# Sheet1.net
KiCad netlist of a schematic drawn in Altium Designer
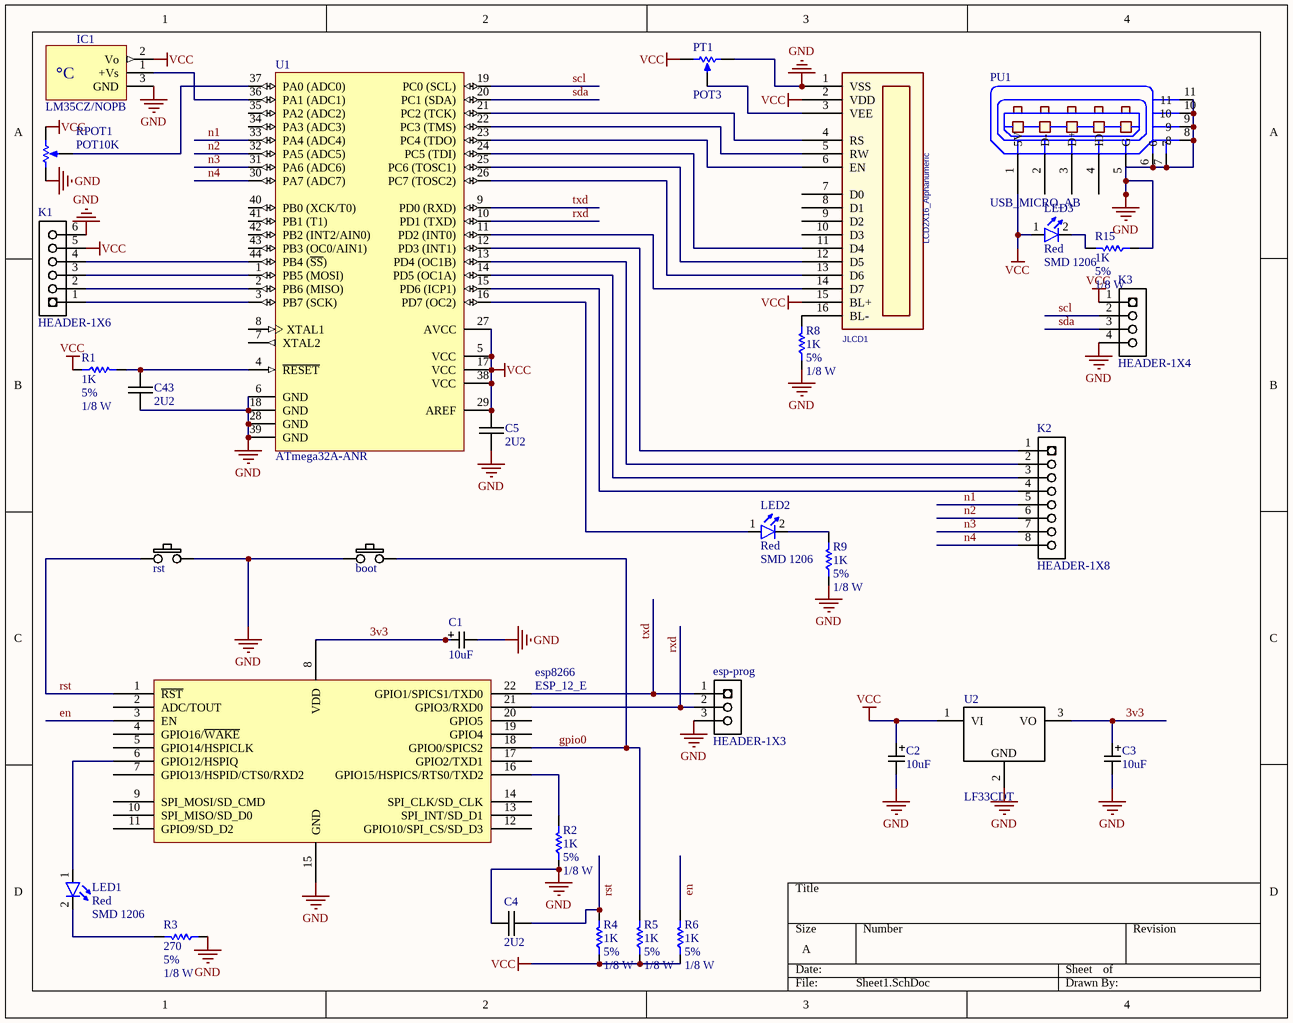
[diagram p0: Sheet1.SchDoc]

(export (version "E")
  (design (tool "Eeschema 10.0.6"))
  (components
    (comp (ref "boot")
      (value "SW-PB-BLACK-SMD")
      (footprint "SW-PB-SMD")
      (description "PUSHBUTTON SWITCH 6MM SMD")
      (libsource (lib "vh_altium_library") (part "SW-PB-BLACK-SMD"))
    )
    (comp (ref "C1")
      (value "10uF")
      (footprint "CAP-B")
      (description "tantalium capacitor")
      (fields (field (name "VOLTAGE") "16V"))
      (libsource (lib "amir_altium_lib") (part "cap"))
    )
    (comp (ref "C2")
      (value "10uF")
      (footprint "CAP-B")
      (description "tantalium capacitor")
      (fields (field (name "VOLTAGE") "16V"))
      (libsource (lib "amir_altium_lib") (part "cap"))
    )
    (comp (ref "C3")
      (value "10uF")
      (footprint "CAP-B")
      (description "tantalium capacitor")
      (fields (field (name "VOLTAGE") "16V"))
      (libsource (lib "amir_altium_lib") (part "cap"))
    )
    (comp (ref "C4")
      (value "2U2")
      (footprint "1206C-GENERIC")
      (description "CAPACITOR 0603 CERAMIC")
      (libsource (lib "vh_altium_library") (part "1206C-2U2-50V"))
    )
    (comp (ref "C5")
      (value "2U2")
      (footprint "1206C-GENERIC")
      (description "CAPACITOR 0603 CERAMIC")
      (libsource (lib "vh_altium_library") (part "1206C-2U2-50V"))
    )
    (comp (ref "C43")
      (value "2U2")
      (footprint "1206C-GENERIC")
      (description "CAPACITOR 0603 CERAMIC")
      (libsource (lib "vh_altium_library") (part "1206C-2U2-50V"))
    )
    (comp (ref "esp-prog")
      (value "HEADER-1X3")
      (footprint "HEADER-1X3")
      (libsource (lib "vh_altium_library") (part "HEADER-1X3"))
    )
    (comp (ref "esp8266")
      (value "ESP_12_E")
      (footprint "ESP_12_E")
      (description "ESP-12 Wi-Fi Module by AI-Thinker")
      (libsource (lib "Morteza lib") (part "ESP_12_E"))
    )
    (comp (ref "IC1")
      (value "LM35CZ/NOPB")
      (footprint "TO-92AA-P127")
      (description "Precision Centigrade Temperature Sensor")
      (fields (field (name "MANUFACTURER") "NATIONAL SEMICONDUCTOR") (field (name "AUTHOR") "CERN DEM JLC"))
      (libsource (lib "Sensors") (part "LM35CZ/NOPB"))
    )
    (comp (ref "JLCD1") (value "LCD2X16_Alphanumeric") (libsource (lib "ALL") (part "LCD2X16_Alphanumeric")))
    (comp (ref "K1")
      (value "HEADER-1X6")
      (footprint "HEADER-1X6")
      (libsource (lib "vh_altium_library") (part "HEADER-1X6"))
    )
    (comp (ref "K2")
      (value "HEADER-1X8")
      (footprint "HEADER-1X8")
      (libsource (lib "vh_altium_library") (part "HEADER-1X8"))
    )
    (comp (ref "K3")
      (value "HEADER-1X4")
      (footprint "HEADER-1X4")
      (libsource (lib "vh_altium_library") (part "HEADER-1X4"))
    )
    (comp (ref "LED1")
      (value "Red")
      (footprint "LED SMD 1206")
      (description "LED")
      (fields
        (field (name "COLOR") "Red")
        (field (name "SIZE") "SMD 1206")
        (field (name "DESIGNER") "Saeid Jorablo")
      )
      (libsource (lib "Electrovolt Lib") (part "LED"))
    )
    (comp (ref "LED2")
      (value "Red")
      (footprint "LED SMD 1206")
      (description "LED")
      (fields
        (field (name "COLOR") "Red")
        (field (name "SIZE") "SMD 1206")
        (field (name "DESIGNER") "Saeid Jorablo")
      )
      (libsource (lib "Electrovolt Lib") (part "LED"))
    )
    (comp (ref "LED3")
      (value "Red")
      (footprint "LED SMD 1206")
      (description "LED")
      (fields
        (field (name "COLOR") "Red")
        (field (name "SIZE") "SMD 1206")
        (field (name "DESIGNER") "Saeid Jorablo")
      )
      (libsource (lib "Electrovolt Lib") (part "LED"))
    )
    (comp (ref "PT1")
      (value "POT3")
      (footprint "POT3")
      (description "Variable Potentiometer top adjust")
      (fields (field (name "DESIGNER") "Seyed Mohsen Ghasemian"))
      (libsource (lib "usefully_Library") (part "POT3"))
    )
    (comp (ref "PU1")
      (value "USB_MICRO_AB")
      (footprint "UUSB_AB_BM_SHS")
      (libsource (lib "ALL") (part "USB_MICRO_AB"))
    )
    (comp (ref "R1")
      (value "1K")
      (footprint "RES 1206 (3216X08L)")
      (description "Resistor")
      (fields (field (name "TOLERANCE") "5%") (field (name "POWER") "1/8 W"))
      (libsource (lib "Electrovolt Lib") (part "Resistor"))
    )
    (comp (ref "R2")
      (value "1K")
      (footprint "RES 1206 (3216X08L)")
      (description "Resistor")
      (fields (field (name "TOLERANCE") "5%") (field (name "POWER") "1/8 W"))
      (libsource (lib "Electrovolt Lib") (part "Resistor"))
    )
    (comp (ref "R3")
      (value "270")
      (footprint "RES 1206 (3216X08L)")
      (description "Resistor")
      (fields (field (name "TOLERANCE") "5%") (field (name "POWER") "1/8 W"))
      (libsource (lib "Electrovolt Lib") (part "Resistor"))
    )
    (comp (ref "R4")
      (value "1K")
      (footprint "RES 1206 (3216X08L)")
      (description "Resistor")
      (fields (field (name "TOLERANCE") "5%") (field (name "POWER") "1/8 W"))
      (libsource (lib "Electrovolt Lib") (part "Resistor"))
    )
    (comp (ref "R5")
      (value "1K")
      (footprint "RES 1206 (3216X08L)")
      (description "Resistor")
      (fields (field (name "TOLERANCE") "5%") (field (name "POWER") "1/8 W"))
      (libsource (lib "Electrovolt Lib") (part "Resistor"))
    )
    (comp (ref "R6")
      (value "1K")
      (footprint "RES 1206 (3216X08L)")
      (description "Resistor")
      (fields (field (name "TOLERANCE") "5%") (field (name "POWER") "1/8 W"))
      (libsource (lib "Electrovolt Lib") (part "Resistor"))
    )
    (comp (ref "R8")
      (value "1K")
      (footprint "RES 1206 (3216X08L)")
      (description "Resistor")
      (fields (field (name "TOLERANCE") "5%") (field (name "POWER") "1/8 W"))
      (libsource (lib "Electrovolt Lib") (part "Resistor"))
    )
    (comp (ref "R9")
      (value "1K")
      (footprint "RES 1206 (3216X08L)")
      (description "Resistor")
      (fields (field (name "TOLERANCE") "5%") (field (name "POWER") "1/8 W"))
      (libsource (lib "Electrovolt Lib") (part "Resistor"))
    )
    (comp (ref "R15")
      (value "1K")
      (footprint "RES 1206 (3216X08L)")
      (description "Resistor")
      (fields (field (name "TOLERANCE") "5%") (field (name "POWER") "1/8 W"))
      (libsource (lib "Electrovolt Lib") (part "Resistor"))
    )
    (comp (ref "RPOT1")
      (value "POT10K")
      (footprint "VOL_R")
      (description "Potentiometer")
      (fields (field (name "PUBLISHER") "Altium Limited"))
      (libsource (lib "ALL") (part "RPot"))
    )
    (comp (ref "rst")
      (value "SW-PB-BLACK-SMD")
      (footprint "SW-PB-SMD")
      (description "PUSHBUTTON SWITCH 6MM SMD")
      (libsource (lib "vh_altium_library") (part "SW-PB-BLACK-SMD"))
    )
    (comp (ref "U1")
      (value "ATmega32A-ANR")
      (footprint "44A_N")
      (libsource (lib "Atmel Microcontroller megaAVR") (part "ATmega32A-ANR"))
    )
    (comp (ref "U2")
      (value "LF33CDT")
      (footprint "DPAK")
      (description "Low Drop Voltage Regulator 3.3V")
      (libsource (lib "vh_altium_library") (part "LF33CDT"))
    )
  )
  (nets
    (net (code "1") (name "/3v3") (class "Default")
      (node (ref "C1") (pin "1") (pintype "passive"))
      (node (ref "C3") (pin "1") (pintype "passive"))
      (node (ref "U2") (pin "3") (pinfunction "VO_3") (pintype "passive"))
      (node (ref "esp8266") (pin "8") (pinfunction "VDD_8") (pintype "passive"))
    )
    (net (code "2") (name "/en") (class "Default")
      (node (ref "R6") (pin "2") (pinfunction "2_2") (pintype "passive"))
      (node (ref "esp8266") (pin "3") (pinfunction "EN_3") (pintype "passive"))
    )
    (net (code "3") (name "/gpio0") (class "Default")
      (node (ref "R5") (pin "2") (pinfunction "2_2") (pintype "passive"))
      (node (ref "boot") (pin "2") (pintype "passive"))
      (node (ref "esp8266") (pin "18") (pinfunction "GPIO0/SPICS2_18") (pintype "passive"))
    )
    (net (code "4") (name "/n1") (class "Default")
      (node (ref "K2") (pin "5") (pintype "passive"))
      (node (ref "U1") (pin "33") (pinfunction "PA4_(ADC4)_33") (pintype "bidirectional"))
    )
    (net (code "5") (name "/n2") (class "Default")
      (node (ref "K2") (pin "6") (pintype "passive"))
      (node (ref "U1") (pin "32") (pinfunction "PA5_(ADC5)_32") (pintype "bidirectional"))
    )
    (net (code "6") (name "/n3") (class "Default")
      (node (ref "K2") (pin "7") (pintype "passive"))
      (node (ref "U1") (pin "31") (pinfunction "PA6_(ADC6)_31") (pintype "bidirectional"))
    )
    (net (code "7") (name "/n4") (class "Default")
      (node (ref "K2") (pin "8") (pintype "passive"))
      (node (ref "U1") (pin "30") (pinfunction "PA7_(ADC7)_30") (pintype "bidirectional"))
    )
    (net (code "8") (name "/rst") (class "Default")
      (node (ref "C4") (pin "1") (pintype "passive"))
      (node (ref "R4") (pin "2") (pinfunction "2_2") (pintype "passive"))
      (node (ref "esp8266") (pin "1") (pinfunction "~{RST}_1") (pintype "passive"))
      (node (ref "rst") (pin "1") (pintype "passive"))
    )
    (net (code "9") (name "/rxd") (class "Default")
      (node (ref "U1") (pin "10") (pinfunction "PD1_(TXD)_10") (pintype "bidirectional"))
      (node (ref "esp-prog") (pin "2") (pintype "passive"))
      (node (ref "esp8266") (pin "21") (pinfunction "GPIO3/RXD0_21") (pintype "passive"))
    )
    (net (code "10") (name "/scl") (class "Default")
      (node (ref "K3") (pin "2") (pintype "passive"))
      (node (ref "U1") (pin "19") (pinfunction "PC0_(SCL)_19") (pintype "bidirectional"))
    )
    (net (code "11") (name "/sda") (class "Default")
      (node (ref "K3") (pin "3") (pintype "passive"))
      (node (ref "U1") (pin "20") (pinfunction "PC1_(SDA)_20") (pintype "bidirectional"))
    )
    (net (code "12") (name "/txd") (class "Default")
      (node (ref "U1") (pin "9") (pinfunction "PD0_(RXD)_9") (pintype "bidirectional"))
      (node (ref "esp-prog") (pin "1") (pintype "passive"))
      (node (ref "esp8266") (pin "22") (pinfunction "GPIO1/SPICS1/TXD0_22") (pintype "passive"))
    )
    (net (code "13") (name "GND") (class "Default")
      (node (ref "C1") (pin "2") (pintype "passive"))
      (node (ref "C2") (pin "2") (pintype "passive"))
      (node (ref "C3") (pin "2") (pintype "passive"))
      (node (ref "C4") (pin "2") (pintype "passive"))
      (node (ref "C43") (pin "1") (pintype "passive"))
      (node (ref "C5") (pin "1") (pintype "passive"))
      (node (ref "IC1") (pin "3") (pinfunction "GND_3") (pintype "power_in"))
      (node (ref "JLCD1") (pin "1") (pinfunction "VSS_1") (pintype "passive"))
      (node (ref "K1") (pin "6") (pintype "passive"))
      (node (ref "K3") (pin "4") (pintype "passive"))
      (node (ref "PT1") (pin "2") (pinfunction "BOT_2") (pintype "passive"))
      (node (ref "PU1") (pin "10") (pinfunction "10_10") (pintype "passive"))
      (node (ref "PU1") (pin "11") (pinfunction "11_11") (pintype "passive"))
      (node (ref "PU1") (pin "5") (pinfunction "G_5") (pintype "passive"))
      (node (ref "PU1") (pin "6") (pinfunction "6_6") (pintype "passive"))
      (node (ref "PU1") (pin "7") (pinfunction "7_7") (pintype "passive"))
      (node (ref "PU1") (pin "8") (pinfunction "8_8") (pintype "passive"))
      (node (ref "PU1") (pin "9") (pinfunction "9_9") (pintype "passive"))
      (node (ref "R15") (pin "1") (pinfunction "1_1") (pintype "passive"))
      (node (ref "R2") (pin "1") (pinfunction "1_1") (pintype "passive"))
      (node (ref "R3") (pin "1") (pinfunction "1_1") (pintype "passive"))
      (node (ref "R8") (pin "1") (pinfunction "1_1") (pintype "passive"))
      (node (ref "R9") (pin "1") (pinfunction "1_1") (pintype "passive"))
      (node (ref "RPOT1") (pin "1") (pinfunction "TOP_1") (pintype "passive"))
      (node (ref "U1") (pin "18") (pinfunction "GND_18") (pintype "power_in"))
      (node (ref "U1") (pin "28") (pinfunction "GND_28") (pintype "power_in"))
      (node (ref "U1") (pin "39") (pinfunction "GND_39") (pintype "power_in"))
      (node (ref "U1") (pin "6") (pinfunction "GND_6") (pintype "power_in"))
      (node (ref "U2") (pin "2") (pintype "passive"))
      (node (ref "boot") (pin "1") (pintype "passive"))
      (node (ref "esp-prog") (pin "3") (pintype "passive"))
      (node (ref "esp8266") (pin "15") (pinfunction "GND_15") (pintype "passive"))
      (node (ref "rst") (pin "2") (pintype "passive"))
    )
    (net (code "14") (name "Net-(IC1-+Vs)") (class "Default")
      (node (ref "IC1") (pin "1") (pinfunction "+Vs_1") (pintype "power_in"))
      (node (ref "U1") (pin "36") (pinfunction "PA1_(ADC1)_36") (pintype "bidirectional"))
    )
    (net (code "15") (name "Net-(JLCD1-BL-)") (class "Default")
      (node (ref "JLCD1") (pin "16") (pinfunction "BL-_16") (pintype "passive"))
      (node (ref "R8") (pin "2") (pinfunction "2_2") (pintype "passive"))
    )
    (net (code "16") (name "Net-(JLCD1-D4)") (class "Default")
      (node (ref "JLCD1") (pin "11") (pinfunction "D4_11") (pintype "passive"))
      (node (ref "U1") (pin "24") (pinfunction "PC5_(TDI)_24") (pintype "bidirectional"))
    )
    (net (code "17") (name "Net-(JLCD1-D5)") (class "Default")
      (node (ref "JLCD1") (pin "12") (pinfunction "D5_12") (pintype "passive"))
      (node (ref "U1") (pin "25") (pinfunction "PC6_(TOSC1)_25") (pintype "bidirectional"))
    )
    (net (code "18") (name "Net-(JLCD1-D6)") (class "Default")
      (node (ref "JLCD1") (pin "13") (pinfunction "D6_13") (pintype "passive"))
      (node (ref "U1") (pin "26") (pinfunction "PC7_(TOSC2)_26") (pintype "bidirectional"))
    )
    (net (code "19") (name "Net-(JLCD1-D7)") (class "Default")
      (node (ref "JLCD1") (pin "14") (pinfunction "D7_14") (pintype "passive"))
      (node (ref "U1") (pin "11") (pinfunction "PD2_(INT0)_11") (pintype "bidirectional"))
    )
    (net (code "20") (name "Net-(JLCD1-EN)") (class "Default")
      (node (ref "JLCD1") (pin "6") (pinfunction "EN_6") (pintype "passive"))
      (node (ref "U1") (pin "23") (pinfunction "PC4_(TDO)_23") (pintype "bidirectional"))
    )
    (net (code "21") (name "Net-(JLCD1-RS)") (class "Default")
      (node (ref "JLCD1") (pin "4") (pinfunction "RS_4") (pintype "passive"))
      (node (ref "U1") (pin "21") (pinfunction "PC2_(TCK)_21") (pintype "bidirectional"))
    )
    (net (code "22") (name "Net-(JLCD1-RW)") (class "Default")
      (node (ref "JLCD1") (pin "5") (pinfunction "RW_5") (pintype "passive"))
      (node (ref "U1") (pin "22") (pinfunction "PC3_(TMS)_22") (pintype "bidirectional"))
    )
    (net (code "23") (name "Net-(JLCD1-VEE)") (class "Default")
      (node (ref "JLCD1") (pin "3") (pinfunction "VEE_3") (pintype "passive"))
      (node (ref "PT1") (pin "3") (pinfunction "TAP_3") (pintype "passive"))
    )
    (net (code "24") (name "Net-(LED1-A)") (class "Default")
      (node (ref "LED1") (pin "1") (pinfunction "A_1") (pintype "passive"))
      (node (ref "esp8266") (pin "6") (pinfunction "GPIO12/HSPIQ_6") (pintype "passive"))
    )
    (net (code "25") (name "Net-(LED1-K)") (class "Default")
      (node (ref "LED1") (pin "2") (pinfunction "K_2") (pintype "passive"))
      (node (ref "R3") (pin "2") (pinfunction "2_2") (pintype "passive"))
    )
    (net (code "26") (name "Net-(LED2-A)") (class "Default")
      (node (ref "LED2") (pin "1") (pinfunction "A_1") (pintype "passive"))
      (node (ref "U1") (pin "16") (pinfunction "PD7_(OC2)_16") (pintype "bidirectional"))
    )
    (net (code "27") (name "Net-(LED2-K)") (class "Default")
      (node (ref "LED2") (pin "2") (pinfunction "K_2") (pintype "passive"))
      (node (ref "R9") (pin "2") (pinfunction "2_2") (pintype "passive"))
    )
    (net (code "28") (name "Net-(LED3-K)") (class "Default")
      (node (ref "LED3") (pin "2") (pinfunction "K_2") (pintype "passive"))
      (node (ref "R15") (pin "2") (pinfunction "2_2") (pintype "passive"))
    )
    (net (code "29") (name "Net-(RPOT1-TAP)") (class "Default")
      (node (ref "RPOT1") (pin "2") (pinfunction "TAP_2") (pintype "passive"))
      (node (ref "U1") (pin "37") (pinfunction "PA0_(ADC0)_37") (pintype "bidirectional"))
    )
    (net (code "30") (name "Net-(U1-PB4_(~{SS}))") (class "Default")
      (node (ref "K1") (pin "4") (pintype "passive"))
      (node (ref "U1") (pin "44") (pinfunction "PB4_(~{SS})_44") (pintype "bidirectional"))
    )
    (net (code "31") (name "Net-(U1-PB5_(MOSI))") (class "Default")
      (node (ref "K1") (pin "3") (pintype "passive"))
      (node (ref "U1") (pin "1") (pinfunction "PB5_(MOSI)_1") (pintype "bidirectional"))
    )
    (net (code "32") (name "Net-(U1-PB6_(MISO))") (class "Default")
      (node (ref "K1") (pin "2") (pintype "passive"))
      (node (ref "U1") (pin "2") (pinfunction "PB6_(MISO)_2") (pintype "bidirectional"))
    )
    (net (code "33") (name "Net-(U1-PB7_(SCK))") (class "Default")
      (node (ref "K1") (pin "1") (pintype "passive"))
      (node (ref "U1") (pin "3") (pinfunction "PB7_(SCK)_3") (pintype "bidirectional"))
    )
    (net (code "34") (name "Net-(U1-PD3_(INT1))") (class "Default")
      (node (ref "K2") (pin "1") (pintype "passive"))
      (node (ref "U1") (pin "12") (pinfunction "PD3_(INT1)_12") (pintype "bidirectional"))
    )
    (net (code "35") (name "Net-(U1-PD4_(OC1B))") (class "Default")
      (node (ref "K2") (pin "2") (pintype "passive"))
      (node (ref "U1") (pin "13") (pinfunction "PD4_(OC1B)_13") (pintype "bidirectional"))
    )
    (net (code "36") (name "Net-(U1-PD5_(OC1A))") (class "Default")
      (node (ref "K2") (pin "3") (pintype "passive"))
      (node (ref "U1") (pin "14") (pinfunction "PD5_(OC1A)_14") (pintype "bidirectional"))
    )
    (net (code "37") (name "Net-(U1-PD6_(ICP1))") (class "Default")
      (node (ref "K2") (pin "4") (pintype "passive"))
      (node (ref "U1") (pin "15") (pinfunction "PD6_(ICP1)_15") (pintype "bidirectional"))
    )
    (net (code "38") (name "Net-(U1-~{RESET})") (class "Default")
      (node (ref "C43") (pin "2") (pintype "passive"))
      (node (ref "R1") (pin "2") (pinfunction "2_2") (pintype "passive"))
      (node (ref "U1") (pin "4") (pinfunction "~{RESET}_4") (pintype "input"))
    )
    (net (code "39") (name "Net-(esp8266-GPIO15{slash}HSPICS{slash}RTS0{slash}TXD2)") (class "Default")
      (node (ref "R2") (pin "2") (pinfunction "2_2") (pintype "passive"))
      (node (ref "esp8266") (pin "16") (pinfunction "GPIO15/HSPICS/RTS0/TXD2_16") (pintype "passive"))
    )
    (net (code "40") (name "VCC") (class "Default")
      (node (ref "C2") (pin "1") (pintype "passive"))
      (node (ref "C5") (pin "2") (pintype "passive"))
      (node (ref "IC1") (pin "2") (pinfunction "Vo_2") (pintype "output"))
      (node (ref "JLCD1") (pin "15") (pinfunction "BL+_15") (pintype "passive"))
      (node (ref "JLCD1") (pin "2") (pinfunction "VDD_2") (pintype "passive"))
      (node (ref "K1") (pin "5") (pintype "passive"))
      (node (ref "K3") (pin "1") (pintype "passive"))
      (node (ref "LED3") (pin "1") (pinfunction "A_1") (pintype "passive"))
      (node (ref "PT1") (pin "1") (pinfunction "TOP_1") (pintype "passive"))
      (node (ref "PU1") (pin "1") (pinfunction "5V_1") (pintype "passive"))
      (node (ref "R1") (pin "1") (pinfunction "1_1") (pintype "passive"))
      (node (ref "R4") (pin "1") (pinfunction "1_1") (pintype "passive"))
      (node (ref "R5") (pin "1") (pinfunction "1_1") (pintype "passive"))
      (node (ref "R6") (pin "1") (pinfunction "1_1") (pintype "passive"))
      (node (ref "RPOT1") (pin "3") (pinfunction "BOT_3") (pintype "passive"))
      (node (ref "U1") (pin "17") (pinfunction "VCC_17") (pintype "power_in"))
      (node (ref "U1") (pin "27") (pinfunction "AVCC_27") (pintype "power_in"))
      (node (ref "U1") (pin "29") (pinfunction "AREF_29") (pintype "power_in"))
      (node (ref "U1") (pin "38") (pinfunction "VCC_38") (pintype "power_in"))
      (node (ref "U1") (pin "5") (pinfunction "VCC_5") (pintype "power_in"))
      (node (ref "U2") (pin "1") (pinfunction "VI_1") (pintype "passive"))
    )
    (net (code "41") (name "unconnected-(JLCD1-D0-Pad7)") (class "Default")
      (node (ref "JLCD1") (pin "7") (pinfunction "D0_7") (pintype "passive"))
    )
    (net (code "42") (name "unconnected-(JLCD1-D1-Pad8)") (class "Default")
      (node (ref "JLCD1") (pin "8") (pinfunction "D1_8") (pintype "passive"))
    )
    (net (code "43") (name "unconnected-(JLCD1-D2-Pad9)") (class "Default")
      (node (ref "JLCD1") (pin "9") (pinfunction "D2_9") (pintype "passive"))
    )
    (net (code "44") (name "unconnected-(JLCD1-D3-Pad10)") (class "Default")
      (node (ref "JLCD1") (pin "10") (pinfunction "D3_10") (pintype "passive"))
    )
    (net (code "45") (name "unconnected-(PU1-D+-Pad3)") (class "Default")
      (node (ref "PU1") (pin "3") (pinfunction "D+_3") (pintype "passive"))
    )
    (net (code "46") (name "unconnected-(PU1-D--Pad2)") (class "Default")
      (node (ref "PU1") (pin "2") (pinfunction "D-_2") (pintype "passive"))
    )
    (net (code "47") (name "unconnected-(PU1-ID-Pad4)") (class "Default")
      (node (ref "PU1") (pin "4") (pinfunction "ID_4") (pintype "passive"))
    )
    (net (code "48") (name "unconnected-(U1-PA2_(ADC2)-Pad35)") (class "Default")
      (node (ref "U1") (pin "35") (pinfunction "PA2_(ADC2)_35") (pintype "bidirectional"))
    )
    (net (code "49") (name "unconnected-(U1-PA3_(ADC3)-Pad34)") (class "Default")
      (node (ref "U1") (pin "34") (pinfunction "PA3_(ADC3)_34") (pintype "bidirectional"))
    )
    (net (code "50") (name "unconnected-(U1-PB0_(XCK{slash}T0)-Pad40)") (class "Default")
      (node (ref "U1") (pin "40") (pinfunction "PB0_(XCK/T0)_40") (pintype "bidirectional"))
    )
    (net (code "51") (name "unconnected-(U1-PB1_(T1)-Pad41)") (class "Default")
      (node (ref "U1") (pin "41") (pinfunction "PB1_(T1)_41") (pintype "bidirectional"))
    )
    (net (code "52") (name "unconnected-(U1-PB2_(INT2{slash}AIN0)-Pad42)") (class "Default")
      (node (ref "U1") (pin "42") (pinfunction "PB2_(INT2/AIN0)_42") (pintype "bidirectional"))
    )
    (net (code "53") (name "unconnected-(U1-PB3_(OC0{slash}AIN1)-Pad43)") (class "Default")
      (node (ref "U1") (pin "43") (pinfunction "PB3_(OC0/AIN1)_43") (pintype "bidirectional"))
    )
    (net (code "54") (name "unconnected-(U1-XTAL1-Pad8)") (class "Default")
      (node (ref "U1") (pin "8") (pinfunction "XTAL1_8") (pintype "input"))
    )
    (net (code "55") (name "unconnected-(U1-XTAL2-Pad7)") (class "Default")
      (node (ref "U1") (pin "7") (pinfunction "XTAL2_7") (pintype "output"))
    )
    (net (code "56") (name "unconnected-(esp8266-ADC{slash}TOUT-Pad2)") (class "Default")
      (node (ref "esp8266") (pin "2") (pinfunction "ADC/TOUT_2") (pintype "passive"))
    )
    (net (code "57") (name "unconnected-(esp8266-GPIO2{slash}TXD1-Pad17)") (class "Default")
      (node (ref "esp8266") (pin "17") (pinfunction "GPIO2/TXD1_17") (pintype "passive"))
    )
    (net (code "58") (name "unconnected-(esp8266-GPIO4-Pad19)") (class "Default")
      (node (ref "esp8266") (pin "19") (pinfunction "GPIO4_19") (pintype "passive"))
    )
    (net (code "59") (name "unconnected-(esp8266-GPIO5-Pad20)") (class "Default")
      (node (ref "esp8266") (pin "20") (pinfunction "GPIO5_20") (pintype "passive"))
    )
    (net (code "60") (name "unconnected-(esp8266-GPIO9{slash}SD_D2-Pad11)") (class "Default")
      (node (ref "esp8266") (pin "11") (pinfunction "GPIO9/SD_D2_11") (pintype "passive"))
    )
    (net (code "61") (name "unconnected-(esp8266-GPIO10{slash}SPI_CS{slash}SD_D3-Pad12)") (class "Default")
      (node (ref "esp8266") (pin "12") (pinfunction "GPIO10/SPI_CS/SD_D3_12") (pintype "passive"))
    )
    (net (code "62") (name "unconnected-(esp8266-GPIO13{slash}HSPID{slash}CTS0{slash}RXD2-Pad7)") (class "Default")
      (node (ref "esp8266") (pin "7") (pinfunction "GPIO13/HSPID/CTS0/RXD2_7") (pintype "passive"))
    )
    (net (code "63") (name "unconnected-(esp8266-GPIO14{slash}HSPICLK-Pad5)") (class "Default")
      (node (ref "esp8266") (pin "5") (pinfunction "GPIO14/HSPICLK_5") (pintype "passive"))
    )
    (net (code "64") (name "unconnected-(esp8266-GPIO16{slash}~{WAKE}-Pad4)") (class "Default")
      (node (ref "esp8266") (pin "4") (pinfunction "GPIO16/~{WAKE}_4") (pintype "passive"))
    )
    (net (code "65") (name "unconnected-(esp8266-SPI_CLK{slash}SD_CLK-Pad14)") (class "Default")
      (node (ref "esp8266") (pin "14") (pinfunction "SPI_CLK/SD_CLK_14") (pintype "passive"))
    )
    (net (code "66") (name "unconnected-(esp8266-SPI_INT{slash}SD_D1-Pad13)") (class "Default")
      (node (ref "esp8266") (pin "13") (pinfunction "SPI_INT/SD_D1_13") (pintype "passive"))
    )
    (net (code "67") (name "unconnected-(esp8266-SPI_MISO{slash}SD_D0-Pad10)") (class "Default")
      (node (ref "esp8266") (pin "10") (pinfunction "SPI_MISO/SD_D0_10") (pintype "passive"))
    )
    (net (code "68") (name "unconnected-(esp8266-SPI_MOSI{slash}SD_CMD-Pad9)") (class "Default")
      (node (ref "esp8266") (pin "9") (pinfunction "SPI_MOSI/SD_CMD_9") (pintype "passive"))
    )
  )
)
